# SpeechStorageModuleV10.net
KiCad netlist of a schematic drawn in EAGLE
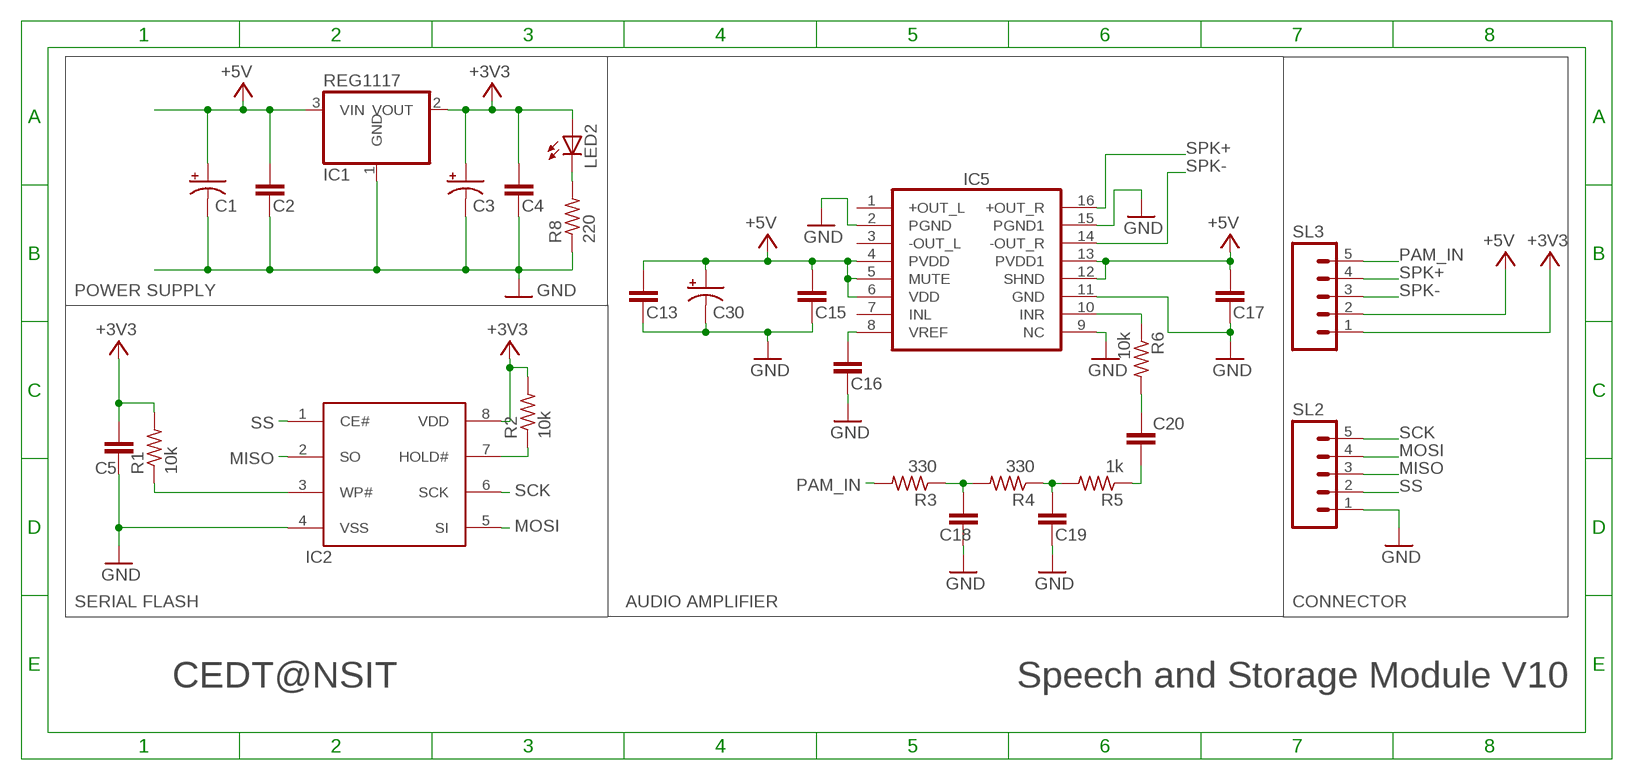
[diagram p0: schematic, sheet 1]

(export (version "E")
  (design (tool "Eeschema 10.0.6"))
  (components
    (comp (ref "C1")
      (value "10u")
      (footprint "eagle-import:C_6032-28R")
      (libsource (lib "eagle-import") (part "CAP_POL_10V"))
    )
    (comp (ref "C2")
      (value "0.1uF")
      (footprint "eagle-import:C1206")
      (libsource (lib "eagle-import") (part "rcl_C-EUC1206"))
    )
    (comp (ref "C3")
      (value "10u")
      (footprint "eagle-import:C_6032-28R")
      (libsource (lib "eagle-import") (part "CAP_POL_10V"))
    )
    (comp (ref "C4")
      (value "0.1uF")
      (footprint "eagle-import:C1206")
      (libsource (lib "eagle-import") (part "rcl_C-EUC1206"))
    )
    (comp (ref "C5")
      (value "0.1u")
      (footprint "eagle-import:C0805")
      (libsource (lib "eagle-import") (part "rcl_C-EUC0805"))
    )
    (comp (ref "C13")
      (value "1uf")
      (footprint "eagle-import:C1206")
      (libsource (lib "eagle-import") (part "rcl_C-EUC1206"))
    )
    (comp (ref "C15")
      (value "1uf")
      (footprint "eagle-import:C1206")
      (libsource (lib "eagle-import") (part "rcl_C-EUC1206"))
    )
    (comp (ref "C16")
      (value "0.1uf")
      (footprint "eagle-import:C1206")
      (libsource (lib "eagle-import") (part "rcl_C-EUC1206"))
    )
    (comp (ref "C17")
      (value "1uf")
      (footprint "eagle-import:C1206")
      (libsource (lib "eagle-import") (part "rcl_C-EUC1206"))
    )
    (comp (ref "C18")
      (value "0.1u")
      (footprint "eagle-import:C0805")
      (libsource (lib "eagle-import") (part "C-EUC0805"))
    )
    (comp (ref "C19")
      (value "0.1uf")
      (footprint "eagle-import:C0805")
      (libsource (lib "eagle-import") (part "C-EUC0805"))
    )
    (comp (ref "C20")
      (value "0.47uF")
      (footprint "eagle-import:C0805")
      (libsource (lib "eagle-import") (part "rcl_C-EUC0805"))
    )
    (comp (ref "C30")
      (value "100u")
      (footprint "eagle-import:C_6032-28R")
      (libsource (lib "eagle-import") (part "CAP_POL_10V"))
    )
    (comp (ref "IC1")
      (value "REG1117")
      (footprint "eagle-import:SOT223")
      (libsource (lib "eagle-import") (part "REG1117"))
    )
    (comp (ref "IC2")
      (value "SST25VF040B_SPI_FLASH")
      (footprint "eagle-import:SOIC08")
      (libsource (lib "eagle-import") (part "SST25VF040B_SPI_FLASH"))
    )
    (comp (ref "IC5")
      (value "PAM8403")
      (footprint "eagle-import:SOP-16")
      (libsource (lib "eagle-import") (part "PAM8403"))
    )
    (comp (ref "LED2")
      (value "LED0805")
      (footprint "eagle-import:CHIPLED_0805")
      (libsource (lib "eagle-import") (part "LED0805"))
    )
    (comp (ref "R1")
      (value "10k")
      (footprint "eagle-import:R0805")
      (libsource (lib "eagle-import") (part "RESISTOR0805"))
    )
    (comp (ref "R2")
      (value "10k")
      (footprint "eagle-import:R0805")
      (libsource (lib "eagle-import") (part "RESISTOR0805"))
    )
    (comp (ref "R3")
      (value "330")
      (footprint "eagle-import:R0805")
      (libsource (lib "eagle-import") (part "RESISTOR0805"))
    )
    (comp (ref "R4")
      (value "330")
      (footprint "eagle-import:R0805")
      (libsource (lib "eagle-import") (part "RESISTOR0805"))
    )
    (comp (ref "R5")
      (value "1k")
      (footprint "eagle-import:R0805")
      (libsource (lib "eagle-import") (part "RESISTOR0805"))
    )
    (comp (ref "R6")
      (value "10k")
      (footprint "eagle-import:R0805")
      (libsource (lib "eagle-import") (part "RESISTOR0805"))
    )
    (comp (ref "R8")
      (value "220")
      (footprint "eagle-import:R0805")
      (libsource (lib "eagle-import") (part "RESISTOR0805"))
    )
    (comp (ref "SL2")
      (value "M05")
      (footprint "eagle-import:05P")
      (libsource (lib "eagle-import") (part "M05"))
    )
    (comp (ref "SL3")
      (value "M05")
      (footprint "eagle-import:05P")
      (libsource (lib "eagle-import") (part "M05"))
    )
  )
  (nets
    (net (code "1") (name "+3V3") (class "Default")
      (node (ref "C3") (pin "+") (pinfunction "+_+") (pintype "passive"))
      (node (ref "C4") (pin "2") (pinfunction "2_2") (pintype "passive"))
      (node (ref "C5") (pin "1") (pinfunction "1_1") (pintype "passive"))
      (node (ref "IC1") (pin "2") (pinfunction "VOUT_2") (pintype "output"))
      (node (ref "IC2") (pin "8") (pinfunction "VDD_8") (pintype "passive"))
      (node (ref "LED2") (pin "A") (pinfunction "A_A") (pintype "passive"))
      (node (ref "R1") (pin "2") (pinfunction "2_2") (pintype "passive"))
      (node (ref "R2") (pin "2") (pinfunction "2_2") (pintype "passive"))
      (node (ref "SL3") (pin "1") (pinfunction "1_1") (pintype "passive"))
    )
    (net (code "2") (name "+5V") (class "Default")
      (node (ref "C1") (pin "+") (pinfunction "+_+") (pintype "passive"))
      (node (ref "C13") (pin "1") (pinfunction "1_1") (pintype "passive"))
      (node (ref "C15") (pin "2") (pinfunction "2_2") (pintype "passive"))
      (node (ref "C17") (pin "2") (pinfunction "2_2") (pintype "passive"))
      (node (ref "C2") (pin "2") (pinfunction "2_2") (pintype "passive"))
      (node (ref "C30") (pin "+") (pinfunction "+_+") (pintype "passive"))
      (node (ref "IC1") (pin "3") (pinfunction "VIN_3") (pintype "input"))
      (node (ref "IC5") (pin "12") (pinfunction "SHND_12") (pintype "output"))
      (node (ref "IC5") (pin "13") (pinfunction "PVDD1_13") (pintype "output"))
      (node (ref "IC5") (pin "4") (pinfunction "PVDD_4") (pintype "input"))
      (node (ref "IC5") (pin "5") (pinfunction "MUTE_5") (pintype "input"))
      (node (ref "IC5") (pin "6") (pinfunction "VDD_6") (pintype "input"))
      (node (ref "SL3") (pin "2") (pinfunction "2_2") (pintype "passive"))
    )
    (net (code "3") (name "/MISO") (class "Default")
      (node (ref "IC2") (pin "2") (pinfunction "SO_2") (pintype "passive"))
      (node (ref "SL2") (pin "3") (pinfunction "3_3") (pintype "passive"))
    )
    (net (code "4") (name "/MOSI") (class "Default")
      (node (ref "IC2") (pin "5") (pinfunction "SI_5") (pintype "passive"))
      (node (ref "SL2") (pin "4") (pinfunction "4_4") (pintype "passive"))
    )
    (net (code "5") (name "/PAM_IN") (class "Default")
      (node (ref "R3") (pin "2") (pinfunction "2_2") (pintype "passive"))
      (node (ref "SL3") (pin "5") (pinfunction "5_5") (pintype "passive"))
    )
    (net (code "6") (name "/SCK") (class "Default")
      (node (ref "IC2") (pin "6") (pinfunction "SCK_6") (pintype "passive"))
      (node (ref "SL2") (pin "5") (pinfunction "5_5") (pintype "passive"))
    )
    (net (code "7") (name "/SPK+") (class "Default")
      (node (ref "IC5") (pin "16") (pinfunction "+OUT_R_16") (pintype "output"))
      (node (ref "SL3") (pin "4") (pinfunction "4_4") (pintype "passive"))
    )
    (net (code "8") (name "/SPK-") (class "Default")
      (node (ref "IC5") (pin "14") (pinfunction "-OUT_R_14") (pintype "output"))
      (node (ref "SL3") (pin "3") (pinfunction "3_3") (pintype "passive"))
    )
    (net (code "9") (name "/SS") (class "Default")
      (node (ref "IC2") (pin "1") (pinfunction "CE#_1") (pintype "passive"))
      (node (ref "SL2") (pin "2") (pinfunction "2_2") (pintype "passive"))
    )
    (net (code "10") (name "GND") (class "Default")
      (node (ref "C1") (pin "-") (pinfunction "-_-") (pintype "passive"))
      (node (ref "C13") (pin "2") (pinfunction "2_2") (pintype "passive"))
      (node (ref "C15") (pin "1") (pinfunction "1_1") (pintype "passive"))
      (node (ref "C16") (pin "2") (pinfunction "2_2") (pintype "passive"))
      (node (ref "C17") (pin "1") (pinfunction "1_1") (pintype "passive"))
      (node (ref "C18") (pin "2") (pinfunction "2_2") (pintype "passive"))
      (node (ref "C19") (pin "2") (pinfunction "2_2") (pintype "passive"))
      (node (ref "C2") (pin "1") (pinfunction "1_1") (pintype "passive"))
      (node (ref "C3") (pin "-") (pinfunction "-_-") (pintype "passive"))
      (node (ref "C30") (pin "-") (pinfunction "-_-") (pintype "passive"))
      (node (ref "C4") (pin "1") (pinfunction "1_1") (pintype "passive"))
      (node (ref "C5") (pin "2") (pinfunction "2_2") (pintype "passive"))
      (node (ref "IC1") (pin "1") (pinfunction "GND_1") (pintype "power_in"))
      (node (ref "IC2") (pin "4") (pinfunction "VSS_4") (pintype "passive"))
      (node (ref "IC5") (pin "11") (pinfunction "GND_11") (pintype "output"))
      (node (ref "IC5") (pin "15") (pinfunction "PGND1_15") (pintype "output"))
      (node (ref "IC5") (pin "2") (pinfunction "PGND_2") (pintype "input"))
      (node (ref "IC5") (pin "9") (pinfunction "NC_9") (pintype "output"))
      (node (ref "R8") (pin "1") (pinfunction "1_1") (pintype "passive"))
      (node (ref "SL2") (pin "1") (pinfunction "1_1") (pintype "passive"))
    )
    (net (code "11") (name "Net-(C18-Pad1)") (class "Default")
      (node (ref "C18") (pin "1") (pinfunction "1_1") (pintype "passive"))
      (node (ref "R3") (pin "1") (pinfunction "1_1") (pintype "passive"))
      (node (ref "R4") (pin "2") (pinfunction "2_2") (pintype "passive"))
    )
    (net (code "12") (name "Net-(C19-Pad1)") (class "Default")
      (node (ref "C19") (pin "1") (pinfunction "1_1") (pintype "passive"))
      (node (ref "R4") (pin "1") (pinfunction "1_1") (pintype "passive"))
      (node (ref "R5") (pin "2") (pinfunction "2_2") (pintype "passive"))
    )
    (net (code "13") (name "Net-(C20-Pad1)") (class "Default")
      (node (ref "C20") (pin "1") (pinfunction "1_1") (pintype "passive"))
      (node (ref "R5") (pin "1") (pinfunction "1_1") (pintype "passive"))
    )
    (net (code "14") (name "Net-(C20-Pad2)") (class "Default")
      (node (ref "C20") (pin "2") (pinfunction "2_2") (pintype "passive"))
      (node (ref "R6") (pin "2") (pinfunction "2_2") (pintype "passive"))
    )
    (net (code "15") (name "Net-(IC2-HOLD#)") (class "Default")
      (node (ref "IC2") (pin "7") (pinfunction "HOLD#_7") (pintype "passive"))
      (node (ref "R2") (pin "1") (pinfunction "1_1") (pintype "passive"))
    )
    (net (code "16") (name "Net-(IC2-WP#)") (class "Default")
      (node (ref "IC2") (pin "3") (pinfunction "WP#_3") (pintype "passive"))
      (node (ref "R1") (pin "1") (pinfunction "1_1") (pintype "passive"))
    )
    (net (code "17") (name "Net-(IC5-INR)") (class "Default")
      (node (ref "IC5") (pin "10") (pinfunction "INR_10") (pintype "output"))
      (node (ref "R6") (pin "1") (pinfunction "1_1") (pintype "passive"))
    )
    (net (code "18") (name "Net-(IC5-VREF)") (class "Default")
      (node (ref "C16") (pin "1") (pinfunction "1_1") (pintype "passive"))
      (node (ref "IC5") (pin "8") (pinfunction "VREF_8") (pintype "input"))
    )
    (net (code "19") (name "Net-(LED2-PadC)") (class "Default")
      (node (ref "LED2") (pin "C") (pinfunction "C_C") (pintype "passive"))
      (node (ref "R8") (pin "2") (pinfunction "2_2") (pintype "passive"))
    )
    (net (code "20") (name "unconnected-(IC5-+OUT_L-Pad1)") (class "Default")
      (node (ref "IC5") (pin "1") (pinfunction "+OUT_L_1") (pintype "input"))
    )
    (net (code "21") (name "unconnected-(IC5--OUT_L-Pad3)") (class "Default")
      (node (ref "IC5") (pin "3") (pinfunction "-OUT_L_3") (pintype "input"))
    )
    (net (code "22") (name "unconnected-(IC5-INL-Pad7)") (class "Default")
      (node (ref "IC5") (pin "7") (pinfunction "INL_7") (pintype "input"))
    )
  )
)
